# Mini_Function_Generator_and_Counter.net
KiCad netlist of a schematic drawn in EAGLE
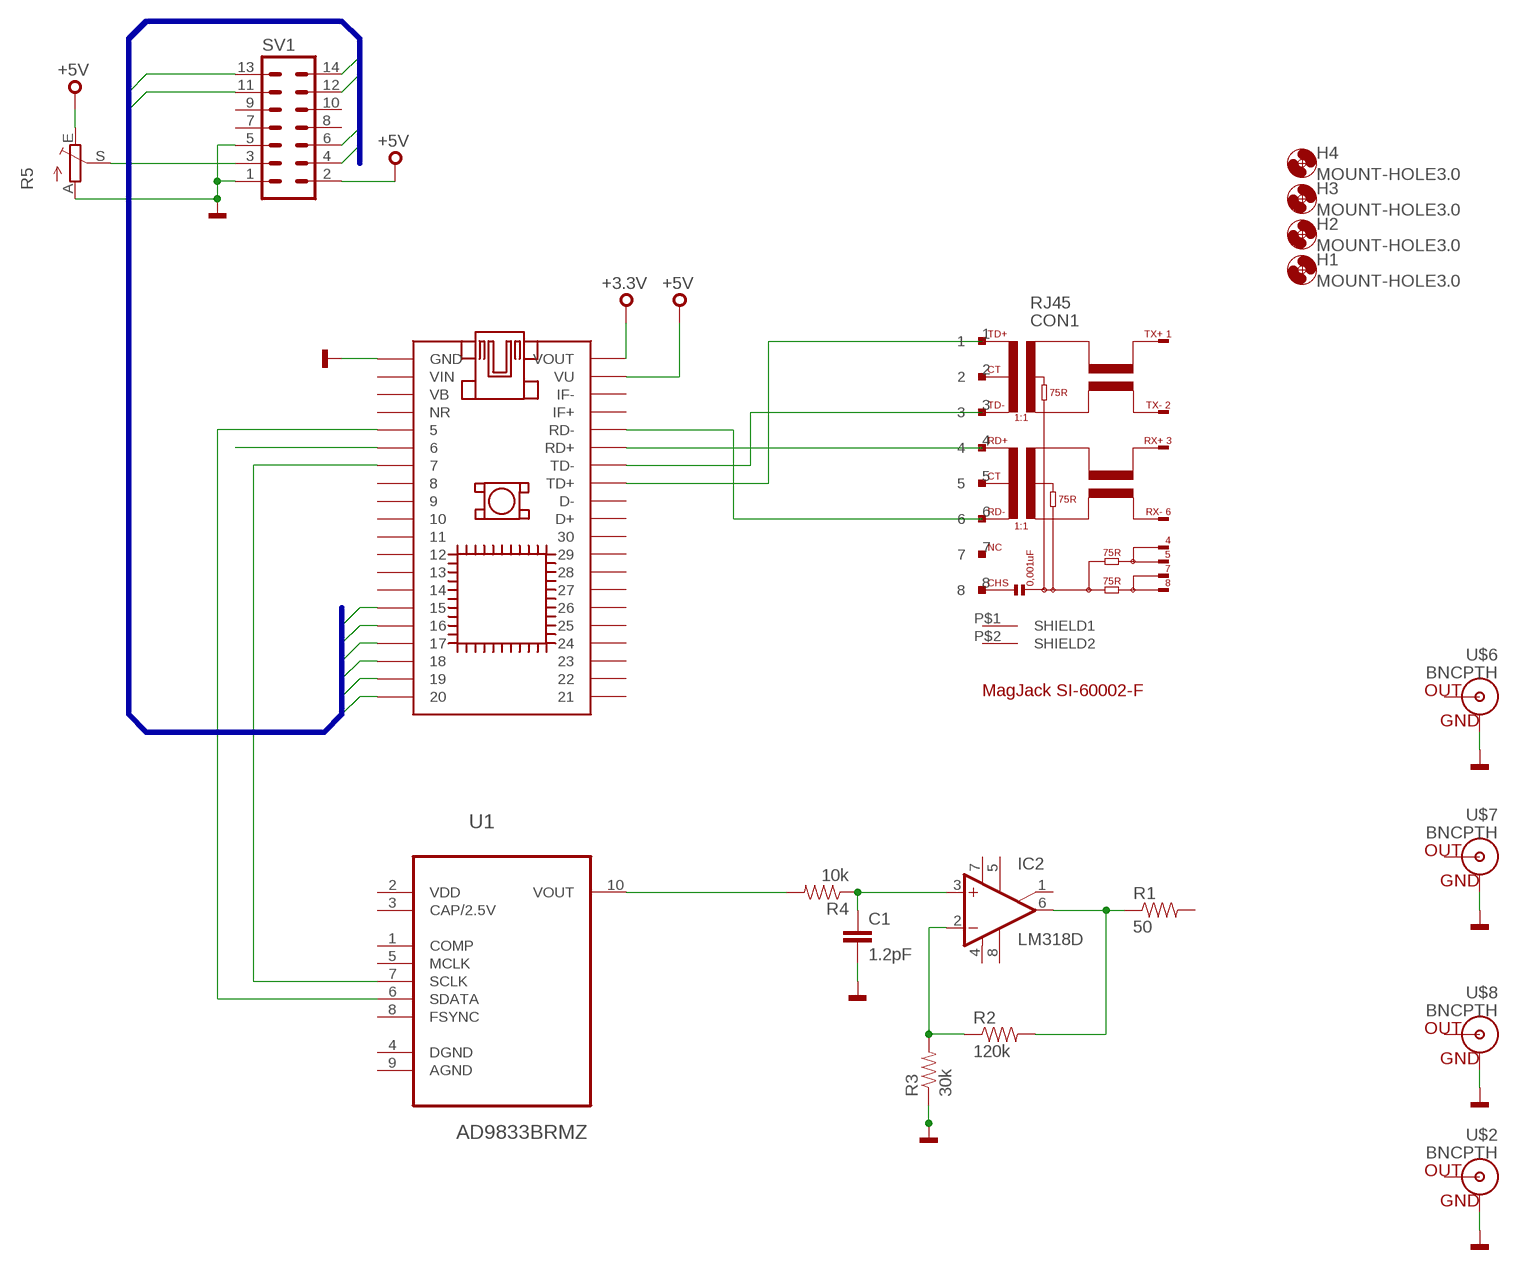
[diagram p0: schematic, sheet 1]

(export (version "E")
  (design (tool "Eeschema 10.0.6"))
  (components
    (comp (ref "C1")
      (value "1.2pF")
      (footprint "eagle-import:0805")
      (libsource (lib "eagle-import") (part "CAP0805"))
    )
    (comp (ref "CON1")
      (value "RJ45")
      (footprint "eagle-import:RJ45")
      (libsource (lib "eagle-import") (part "RJ45"))
    )
    (comp (ref "H1")
      (value "MOUNT-HOLE3.0")
      (footprint "eagle-import:3,0")
      (libsource (lib "eagle-import") (part "MOUNT-HOLE3.0"))
    )
    (comp (ref "H2")
      (value "MOUNT-HOLE3.0")
      (footprint "eagle-import:3,0")
      (libsource (lib "eagle-import") (part "MOUNT-HOLE3.0"))
    )
    (comp (ref "H3")
      (value "MOUNT-HOLE3.0")
      (footprint "eagle-import:3,0")
      (libsource (lib "eagle-import") (part "MOUNT-HOLE3.0"))
    )
    (comp (ref "H4")
      (value "MOUNT-HOLE3.0")
      (footprint "eagle-import:3,0")
      (libsource (lib "eagle-import") (part "MOUNT-HOLE3.0"))
    )
    (comp (ref "IC1")
      (value "MBED-SOCKET")
      (footprint "eagle-import:MBED-SOCKET")
      (libsource (lib "eagle-import") (part "MBED-SOCKET"))
    )
    (comp (ref "IC2")
      (value "LM318D")
      (footprint "eagle-import:SO08")
      (libsource (lib "eagle-import") (part "LM318D"))
    )
    (comp (ref "R1")
      (value "50")
      (footprint "eagle-import:0805")
      (libsource (lib "eagle-import") (part "RESISTOR"))
    )
    (comp (ref "R2")
      (value "120k")
      (footprint "eagle-import:0805")
      (libsource (lib "eagle-import") (part "RESISTOR"))
    )
    (comp (ref "R3")
      (value "30k")
      (footprint "eagle-import:0805")
      (libsource (lib "eagle-import") (part "RESISTOR"))
    )
    (comp (ref "R4")
      (value "10k")
      (footprint "eagle-import:0805")
      (libsource (lib "eagle-import") (part "RESISTOR"))
    )
    (comp (ref "R5")
      (value "TRIM_EU-PT10")
      (footprint "eagle-import:PT-10")
      (libsource (lib "eagle-import") (part "TRIM_EU-PT10"))
    )
    (comp (ref "SV1")
      (value "14PL")
      (footprint "eagle-import:14PL")
      (libsource (lib "eagle-import") (part "14PL"))
    )
    (comp (ref "U$2")
      (value "BNCPTH")
      (footprint "eagle-import:BNC")
      (libsource (lib "eagle-import") (part "BNCPTH"))
    )
    (comp (ref "U$6")
      (value "BNCPTH")
      (footprint "eagle-import:BNC")
      (libsource (lib "eagle-import") (part "BNCPTH"))
    )
    (comp (ref "U$7")
      (value "BNCPTH")
      (footprint "eagle-import:BNC")
      (libsource (lib "eagle-import") (part "BNCPTH"))
    )
    (comp (ref "U$8")
      (value "BNCPTH")
      (footprint "eagle-import:BNC")
      (libsource (lib "eagle-import") (part "BNCPTH"))
    )
    (comp (ref "U1")
      (value "AD9833BRMZ")
      (footprint "eagle-import:SOP50P490X110-10N")
      (libsource (lib "eagle-import") (part "AD9833BRMZ"))
    )
  )
  (nets
    (net (code "1") (name "+3.3V") (class "Default")
      (node (ref "IC1") (pin "P$40") (pinfunction "VOUT_P$40") (pintype "bidirectional"))
    )
    (net (code "2") (name "+5V") (class "Default")
      (node (ref "IC1") (pin "P$39") (pinfunction "VU_P$39") (pintype "bidirectional"))
      (node (ref "R5") (pin "E") (pinfunction "E_E") (pintype "passive"))
      (node (ref "SV1") (pin "2") (pinfunction "2_2") (pintype "passive"))
    )
    (net (code "3") (name "/D4") (class "Default")
      (node (ref "IC1") (pin "P$17") (pinfunction "17_P$17") (pintype "bidirectional"))
      (node (ref "SV1") (pin "11") (pinfunction "11_11") (pintype "passive"))
    )
    (net (code "4") (name "/D5") (class "Default")
      (node (ref "IC1") (pin "P$18") (pinfunction "18_P$18") (pintype "bidirectional"))
      (node (ref "SV1") (pin "12") (pinfunction "12_12") (pintype "passive"))
    )
    (net (code "5") (name "/D6") (class "Default")
      (node (ref "IC1") (pin "P$19") (pinfunction "19_P$19") (pintype "bidirectional"))
      (node (ref "SV1") (pin "13") (pinfunction "13_13") (pintype "passive"))
    )
    (net (code "6") (name "/D7") (class "Default")
      (node (ref "IC1") (pin "P$20") (pinfunction "20_P$20") (pintype "bidirectional"))
      (node (ref "SV1") (pin "14") (pinfunction "14_14") (pintype "passive"))
    )
    (net (code "7") (name "/E") (class "Default")
      (node (ref "IC1") (pin "P$16") (pinfunction "16_P$16") (pintype "bidirectional"))
      (node (ref "SV1") (pin "4") (pinfunction "4_4") (pintype "passive"))
    )
    (net (code "8") (name "/RS") (class "Default")
      (node (ref "IC1") (pin "P$15") (pinfunction "15_P$15") (pintype "bidirectional"))
      (node (ref "SV1") (pin "6") (pinfunction "6_6") (pintype "passive"))
    )
    (net (code "9") (name "/V+") (class "Default")
      (node (ref "IC2") (pin "7") (pinfunction "V+_7") (pintype "power_in"))
    )
    (net (code "10") (name "/V-") (class "Default")
      (node (ref "IC2") (pin "4") (pinfunction "V-_4") (pintype "power_in"))
    )
    (net (code "11") (name "/VDD") (class "Default")
      (node (ref "U1") (pin "2") (pinfunction "VDD_2") (pintype "power_in"))
    )
    (net (code "12") (name "GND") (class "Default")
      (node (ref "C1") (pin "2") (pinfunction "2_2") (pintype "passive"))
      (node (ref "IC1") (pin "P$1") (pinfunction "GND_P$1") (pintype "bidirectional"))
      (node (ref "R3") (pin "1") (pinfunction "1_1") (pintype "passive"))
      (node (ref "R5") (pin "A") (pinfunction "A_A") (pintype "passive"))
      (node (ref "SV1") (pin "1") (pinfunction "1_1") (pintype "passive"))
      (node (ref "SV1") (pin "5") (pinfunction "5_5") (pintype "passive"))
      (node (ref "U$2") (pin "GND") (pinfunction "GND_GND") (pintype "bidirectional"))
      (node (ref "U$6") (pin "GND") (pinfunction "GND_GND") (pintype "bidirectional"))
      (node (ref "U$7") (pin "GND") (pinfunction "GND_GND") (pintype "bidirectional"))
      (node (ref "U$8") (pin "GND") (pinfunction "GND_GND") (pintype "bidirectional"))
    )
    (net (code "13") (name "Net-(IC1-5)") (class "Default")
      (node (ref "IC1") (pin "P$5") (pinfunction "5_P$5") (pintype "bidirectional"))
      (node (ref "U1") (pin "6") (pinfunction "SDATA_6") (pintype "input"))
    )
    (net (code "14") (name "Net-(IC1-7)") (class "Default")
      (node (ref "IC1") (pin "P$7") (pinfunction "7_P$7") (pintype "bidirectional"))
      (node (ref "U1") (pin "7") (pinfunction "SCLK_7") (pintype "input"))
    )
    (net (code "15") (name "Net-(IC1-RD+)") (class "Default")
      (node (ref "CON1") (pin "4") (pinfunction "4_4") (pintype "passive"))
      (node (ref "IC1") (pin "P$35") (pinfunction "RD+_P$35") (pintype "bidirectional"))
    )
    (net (code "16") (name "Net-(IC1-RD-)") (class "Default")
      (node (ref "CON1") (pin "6") (pinfunction "6_6") (pintype "passive"))
      (node (ref "IC1") (pin "P$36") (pinfunction "RD-_P$36") (pintype "bidirectional"))
    )
    (net (code "17") (name "Net-(IC1-TD+)") (class "Default")
      (node (ref "CON1") (pin "1") (pinfunction "1_1") (pintype "passive"))
      (node (ref "IC1") (pin "P$33") (pinfunction "TD+_P$33") (pintype "bidirectional"))
    )
    (net (code "18") (name "Net-(IC1-TD-)") (class "Default")
      (node (ref "CON1") (pin "3") (pinfunction "3_3") (pintype "passive"))
      (node (ref "IC1") (pin "P$34") (pinfunction "TD-_P$34") (pintype "bidirectional"))
    )
    (net (code "19") (name "Net-(IC2-+IN)") (class "Default")
      (node (ref "C1") (pin "1") (pinfunction "1_1") (pintype "passive"))
      (node (ref "IC2") (pin "3") (pinfunction "+IN_3") (pintype "input"))
      (node (ref "R4") (pin "1") (pinfunction "1_1") (pintype "passive"))
    )
    (net (code "20") (name "Net-(IC2--IN)") (class "Default")
      (node (ref "IC2") (pin "2") (pinfunction "-IN_2") (pintype "input"))
      (node (ref "R2") (pin "1") (pinfunction "1_1") (pintype "passive"))
      (node (ref "R3") (pin "2") (pinfunction "2_2") (pintype "passive"))
    )
    (net (code "21") (name "Net-(IC2-OUT)") (class "Default")
      (node (ref "IC2") (pin "6") (pinfunction "OUT_6") (pintype "output"))
      (node (ref "R1") (pin "1") (pinfunction "1_1") (pintype "passive"))
      (node (ref "R2") (pin "2") (pinfunction "2_2") (pintype "passive"))
    )
    (net (code "22") (name "Net-(R5-PadS)") (class "Default")
      (node (ref "R5") (pin "S") (pinfunction "S_S") (pintype "passive"))
      (node (ref "SV1") (pin "3") (pinfunction "3_3") (pintype "passive"))
    )
    (net (code "23") (name "Net-(U1-VOUT)") (class "Default")
      (node (ref "R4") (pin "2") (pinfunction "2_2") (pintype "passive"))
      (node (ref "U1") (pin "10") (pinfunction "VOUT_10") (pintype "output"))
    )
    (net (code "24") (name "unconnected-(CON1-Pad2)") (class "Default")
      (node (ref "CON1") (pin "2") (pinfunction "2_2") (pintype "passive"))
    )
    (net (code "25") (name "unconnected-(CON1-Pad5)") (class "Default")
      (node (ref "CON1") (pin "5") (pinfunction "5_5") (pintype "passive"))
    )
    (net (code "26") (name "unconnected-(CON1-Pad7)") (class "Default")
      (node (ref "CON1") (pin "7") (pinfunction "7_7") (pintype "passive"))
    )
    (net (code "27") (name "unconnected-(CON1-Pad8)") (class "Default")
      (node (ref "CON1") (pin "8") (pinfunction "8_8") (pintype "passive"))
    )
    (net (code "28") (name "unconnected-(CON1-SHIELD1-PadP$1)") (class "Default")
      (node (ref "CON1") (pin "P$1") (pinfunction "SHIELD1_P$1") (pintype "bidirectional"))
    )
    (net (code "29") (name "unconnected-(CON1-SHIELD2-PadP$2)") (class "Default")
      (node (ref "CON1") (pin "P$2") (pinfunction "SHIELD2_P$2") (pintype "bidirectional"))
    )
    (net (code "30") (name "unconnected-(IC1-6-PadP$6)") (class "Default")
      (node (ref "IC1") (pin "P$6") (pinfunction "6_P$6") (pintype "bidirectional"))
    )
    (net (code "31") (name "unconnected-(IC1-8-PadP$8)") (class "Default")
      (node (ref "IC1") (pin "P$8") (pinfunction "8_P$8") (pintype "bidirectional"))
    )
    (net (code "32") (name "unconnected-(IC1-9-PadP$9)") (class "Default")
      (node (ref "IC1") (pin "P$9") (pinfunction "9_P$9") (pintype "bidirectional"))
    )
    (net (code "33") (name "unconnected-(IC1-10-PadP$10)") (class "Default")
      (node (ref "IC1") (pin "P$10") (pinfunction "10_P$10") (pintype "bidirectional"))
    )
    (net (code "34") (name "unconnected-(IC1-11-PadP$11)") (class "Default")
      (node (ref "IC1") (pin "P$11") (pinfunction "11_P$11") (pintype "bidirectional"))
    )
    (net (code "35") (name "unconnected-(IC1-12-PadP$12)") (class "Default")
      (node (ref "IC1") (pin "P$12") (pinfunction "12_P$12") (pintype "bidirectional"))
    )
    (net (code "36") (name "unconnected-(IC1-13-PadP$13)") (class "Default")
      (node (ref "IC1") (pin "P$13") (pinfunction "13_P$13") (pintype "bidirectional"))
    )
    (net (code "37") (name "unconnected-(IC1-14-PadP$14)") (class "Default")
      (node (ref "IC1") (pin "P$14") (pinfunction "14_P$14") (pintype "bidirectional"))
    )
    (net (code "38") (name "unconnected-(IC1-21-PadP$21)") (class "Default")
      (node (ref "IC1") (pin "P$21") (pinfunction "21_P$21") (pintype "bidirectional"))
    )
    (net (code "39") (name "unconnected-(IC1-22-PadP$22)") (class "Default")
      (node (ref "IC1") (pin "P$22") (pinfunction "22_P$22") (pintype "bidirectional"))
    )
    (net (code "40") (name "unconnected-(IC1-23-PadP$23)") (class "Default")
      (node (ref "IC1") (pin "P$23") (pinfunction "23_P$23") (pintype "bidirectional"))
    )
    (net (code "41") (name "unconnected-(IC1-24-PadP$24)") (class "Default")
      (node (ref "IC1") (pin "P$24") (pinfunction "24_P$24") (pintype "bidirectional"))
    )
    (net (code "42") (name "unconnected-(IC1-25-PadP$25)") (class "Default")
      (node (ref "IC1") (pin "P$25") (pinfunction "25_P$25") (pintype "bidirectional"))
    )
    (net (code "43") (name "unconnected-(IC1-26-PadP$26)") (class "Default")
      (node (ref "IC1") (pin "P$26") (pinfunction "26_P$26") (pintype "bidirectional"))
    )
    (net (code "44") (name "unconnected-(IC1-27-PadP$27)") (class "Default")
      (node (ref "IC1") (pin "P$27") (pinfunction "27_P$27") (pintype "bidirectional"))
    )
    (net (code "45") (name "unconnected-(IC1-28-PadP$28)") (class "Default")
      (node (ref "IC1") (pin "P$28") (pinfunction "28_P$28") (pintype "bidirectional"))
    )
    (net (code "46") (name "unconnected-(IC1-29-PadP$29)") (class "Default")
      (node (ref "IC1") (pin "P$29") (pinfunction "29_P$29") (pintype "bidirectional"))
    )
    (net (code "47") (name "unconnected-(IC1-30-PadP$30)") (class "Default")
      (node (ref "IC1") (pin "P$30") (pinfunction "30_P$30") (pintype "bidirectional"))
    )
    (net (code "48") (name "unconnected-(IC1-D+-PadP$31)") (class "Default")
      (node (ref "IC1") (pin "P$31") (pinfunction "D+_P$31") (pintype "bidirectional"))
    )
    (net (code "49") (name "unconnected-(IC1-D--PadP$32)") (class "Default")
      (node (ref "IC1") (pin "P$32") (pinfunction "D-_P$32") (pintype "bidirectional"))
    )
    (net (code "50") (name "unconnected-(IC1-IF+-PadP$37)") (class "Default")
      (node (ref "IC1") (pin "P$37") (pinfunction "IF+_P$37") (pintype "bidirectional"))
    )
    (net (code "51") (name "unconnected-(IC1-IF--PadP$38)") (class "Default")
      (node (ref "IC1") (pin "P$38") (pinfunction "IF-_P$38") (pintype "bidirectional"))
    )
    (net (code "52") (name "unconnected-(IC1-NR-PadP$4)") (class "Default")
      (node (ref "IC1") (pin "P$4") (pinfunction "NR_P$4") (pintype "bidirectional"))
    )
    (net (code "53") (name "unconnected-(IC1-VB-PadP$3)") (class "Default")
      (node (ref "IC1") (pin "P$3") (pinfunction "VB_P$3") (pintype "bidirectional"))
    )
    (net (code "54") (name "unconnected-(IC1-VIN-PadP$2)") (class "Default")
      (node (ref "IC1") (pin "P$2") (pinfunction "VIN_P$2") (pintype "bidirectional"))
    )
    (net (code "55") (name "unconnected-(IC2-CMP-Pad8)") (class "Default")
      (node (ref "IC2") (pin "8") (pinfunction "CMP_8") (pintype "passive"))
    )
    (net (code "56") (name "unconnected-(IC2-ON-Pad5)") (class "Default")
      (node (ref "IC2") (pin "5") (pinfunction "ON_5") (pintype "passive"))
    )
    (net (code "57") (name "unconnected-(IC2-ON{slash}CMP-Pad1)") (class "Default")
      (node (ref "IC2") (pin "1") (pinfunction "ON/CMP_1") (pintype "passive"))
    )
    (net (code "58") (name "unconnected-(R1-Pad2)") (class "Default")
      (node (ref "R1") (pin "2") (pinfunction "2_2") (pintype "passive"))
    )
    (net (code "59") (name "unconnected-(SV1-Pad7)") (class "Default")
      (node (ref "SV1") (pin "7") (pinfunction "7_7") (pintype "passive"))
    )
    (net (code "60") (name "unconnected-(SV1-Pad8)") (class "Default")
      (node (ref "SV1") (pin "8") (pinfunction "8_8") (pintype "passive"))
    )
    (net (code "61") (name "unconnected-(SV1-Pad9)") (class "Default")
      (node (ref "SV1") (pin "9") (pinfunction "9_9") (pintype "passive"))
    )
    (net (code "62") (name "unconnected-(SV1-Pad10)") (class "Default")
      (node (ref "SV1") (pin "10") (pinfunction "10_10") (pintype "passive"))
    )
    (net (code "63") (name "unconnected-(U$2-OUT-PadS)") (class "Default")
      (node (ref "U$2") (pin "S") (pinfunction "OUT_S") (pintype "bidirectional"))
    )
    (net (code "64") (name "unconnected-(U$6-OUT-PadS)") (class "Default")
      (node (ref "U$6") (pin "S") (pinfunction "OUT_S") (pintype "bidirectional"))
    )
    (net (code "65") (name "unconnected-(U$7-OUT-PadS)") (class "Default")
      (node (ref "U$7") (pin "S") (pinfunction "OUT_S") (pintype "bidirectional"))
    )
    (net (code "66") (name "unconnected-(U$8-OUT-PadS)") (class "Default")
      (node (ref "U$8") (pin "S") (pinfunction "OUT_S") (pintype "bidirectional"))
    )
    (net (code "67") (name "unconnected-(U1-AGND-Pad9)") (class "Default")
      (node (ref "U1") (pin "9") (pinfunction "AGND_9") (pintype "passive"))
    )
    (net (code "68") (name "unconnected-(U1-CAP{slash}2.5V-Pad3)") (class "Default")
      (node (ref "U1") (pin "3") (pinfunction "CAP/2.5V_3") (pintype "passive"))
    )
    (net (code "69") (name "unconnected-(U1-COMP-Pad1)") (class "Default")
      (node (ref "U1") (pin "1") (pinfunction "COMP_1") (pintype "passive"))
    )
    (net (code "70") (name "unconnected-(U1-DGND-Pad4)") (class "Default")
      (node (ref "U1") (pin "4") (pinfunction "DGND_4") (pintype "passive"))
    )
    (net (code "71") (name "unconnected-(U1-FSYNC-Pad8)") (class "Default")
      (node (ref "U1") (pin "8") (pinfunction "FSYNC_8") (pintype "input"))
    )
    (net (code "72") (name "unconnected-(U1-MCLK-Pad5)") (class "Default")
      (node (ref "U1") (pin "5") (pinfunction "MCLK_5") (pintype "input"))
    )
  )
)
